# schemat.net
KiCad netlist of a schematic drawn in EAGLE
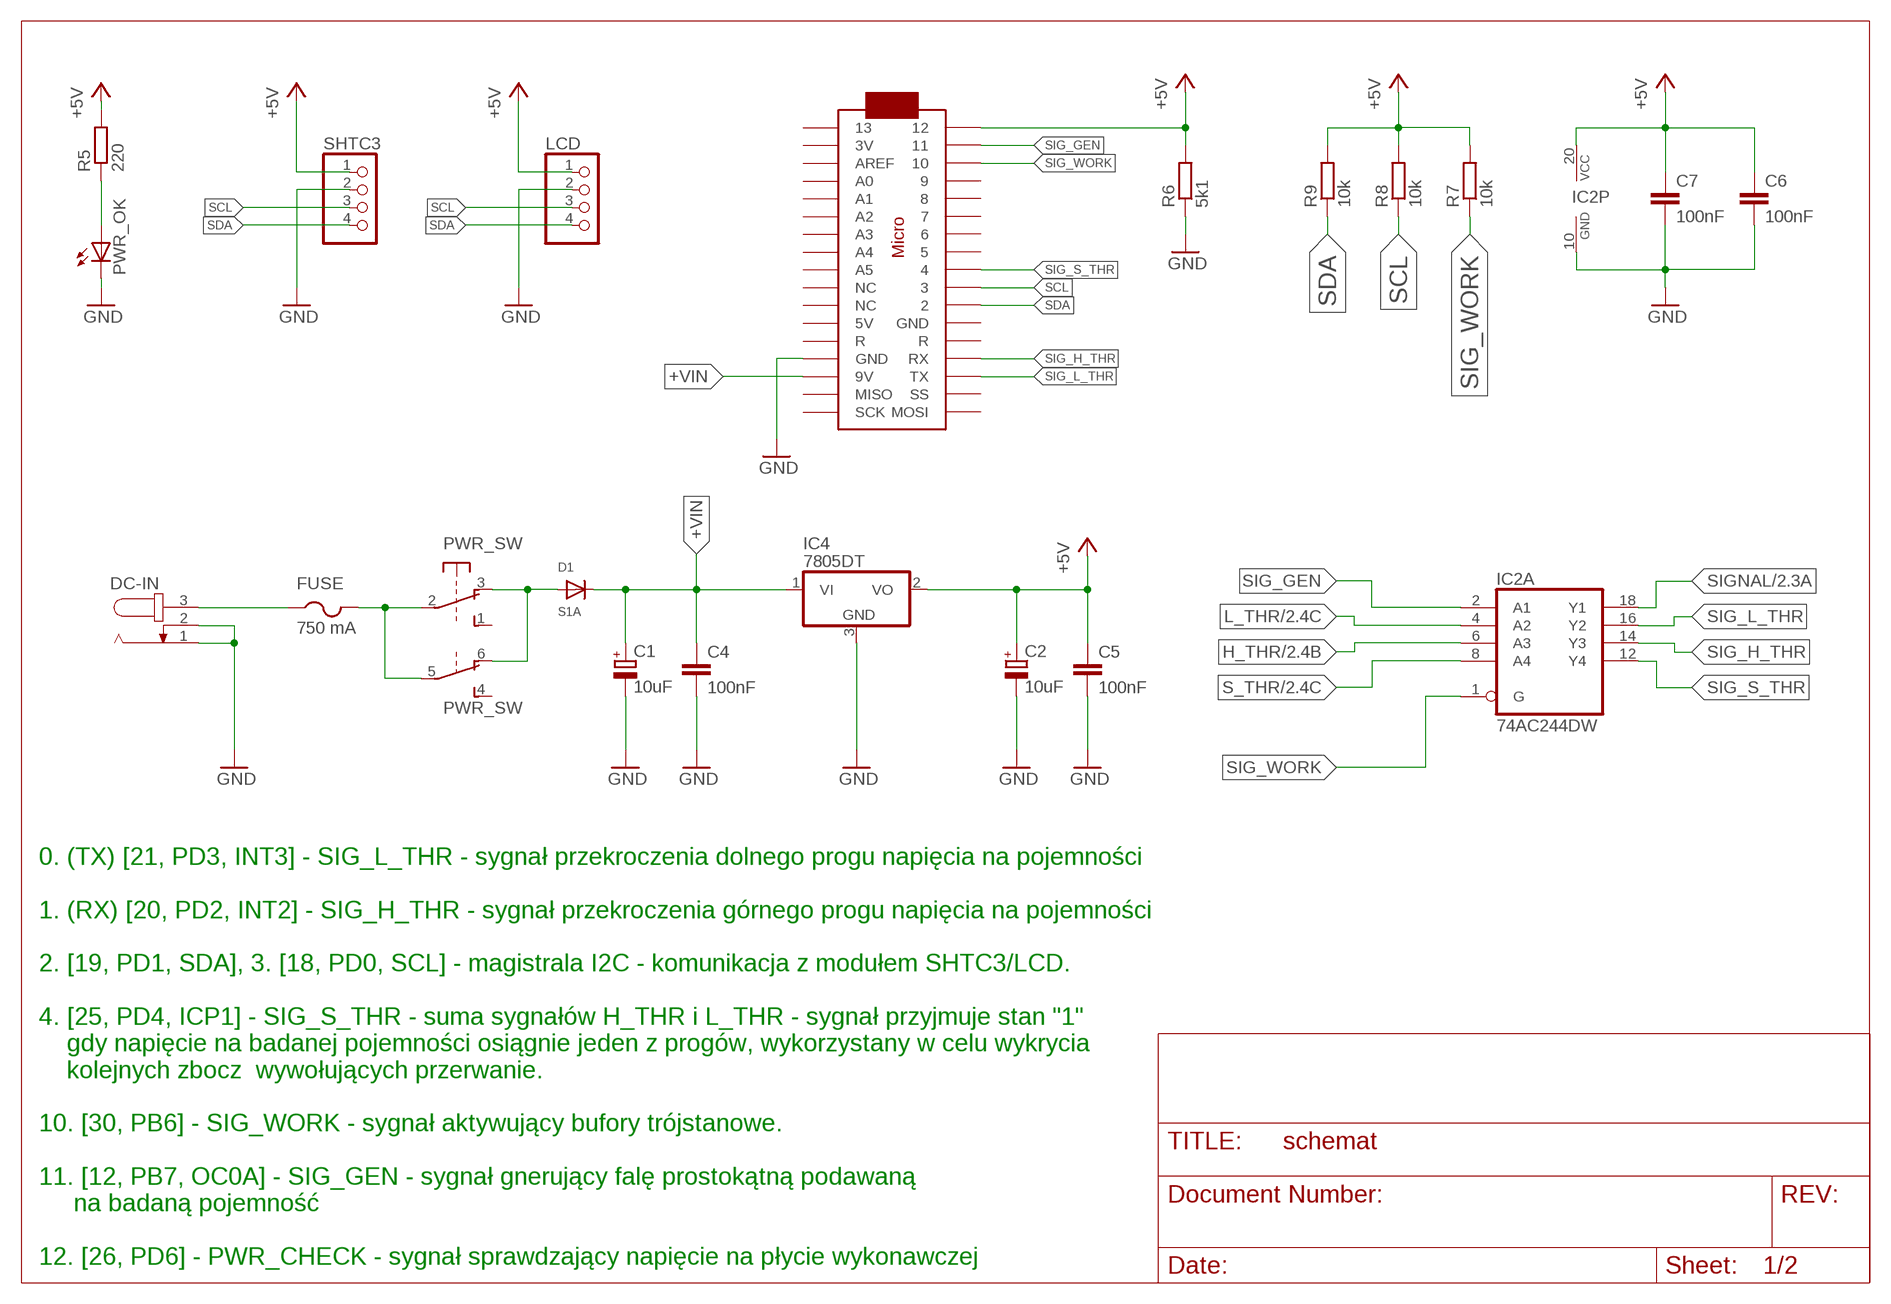
[diagram p0: schematic, sheet 1]
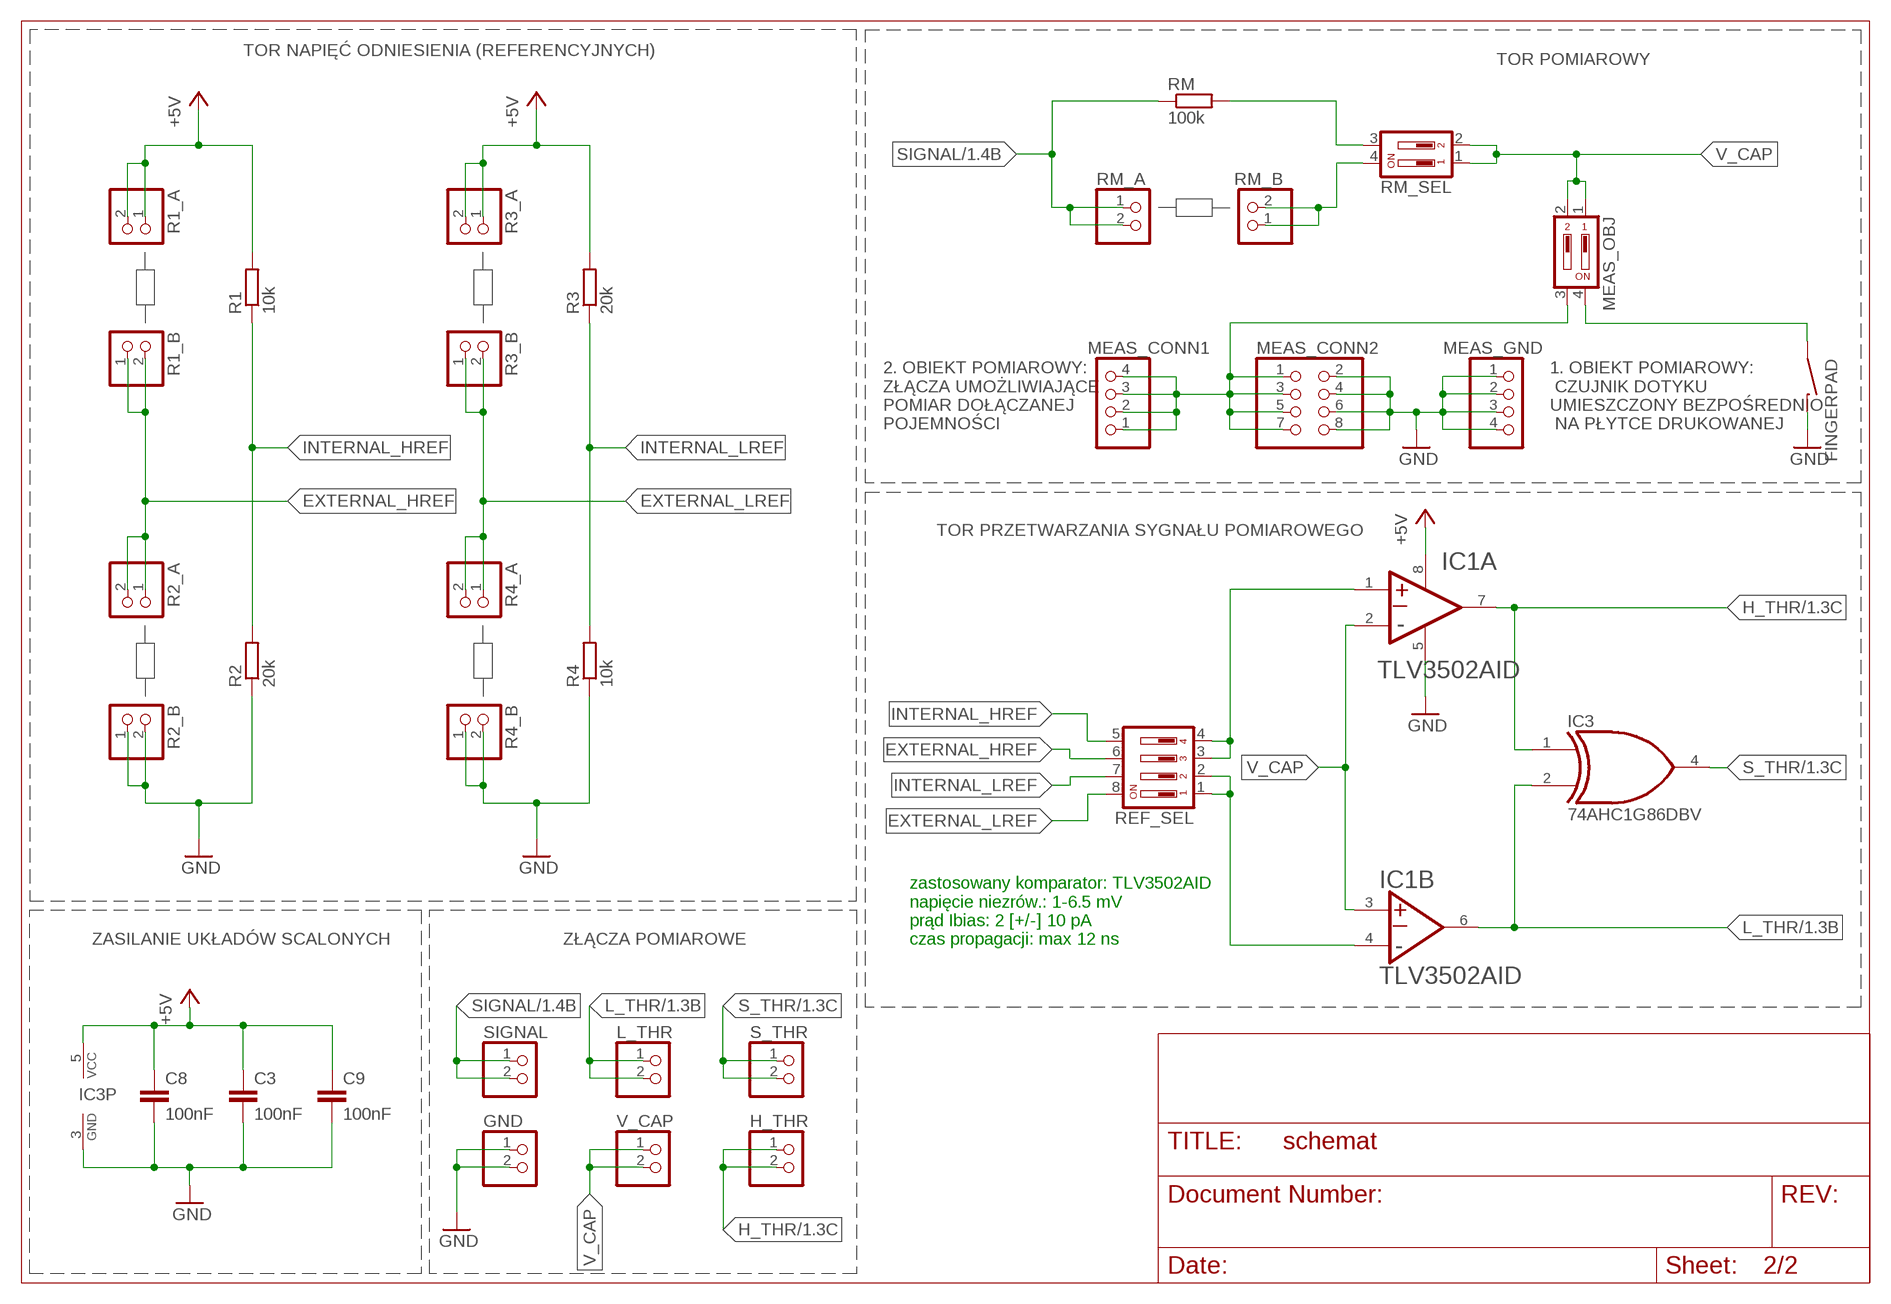
[diagram p1: schematic, sheet 2]

(export (version "E")
  (design (tool "Eeschema 10.0.6"))
  (components
    (comp (ref "C3")
      (value "100nF")
      (footprint "eagle-import:C1206K")
      (libsource (lib "eagle-import") (part "C-EUC1206K"))
    )
    (comp (ref "C8")
      (value "100nF")
      (footprint "eagle-import:C1206K")
      (libsource (lib "eagle-import") (part "C-EUC1206K"))
    )
    (comp (ref "C9")
      (value "100nF")
      (footprint "eagle-import:C1206K")
      (libsource (lib "eagle-import") (part "C-EUC1206K"))
    )
    (comp (ref "FINGERPAD")
      (value "FINGERPAD-2B")
      (footprint "eagle-import:FINGERPAD-2B")
      (libsource (lib "eagle-import") (part "FINGERPAD-2B"))
    )
    (comp (ref "GND")
      (value "PINHD-1X2")
      (footprint "eagle-import:1X02")
      (libsource (lib "eagle-import") (part "PINHD-1X2"))
    )
    (comp (ref "H_THR")
      (value "PINHD-1X2")
      (footprint "eagle-import:1X02")
      (libsource (lib "eagle-import") (part "PINHD-1X2"))
    )
    (comp (ref "IC1")
      (value "TEXAS_INSTRUMENTS_TLV3502AIDTEXAS_INSTRUMENTS_TLV3502AID_0_1")
      (footprint "eagle-import:TEXAS_INSTRUMENTS_TLV3502AID_1")
      (fields
        (field (name "DIGIKEY_PART_NUMBER") "296-18301-5-ND")
        (field (name "MF") "Texas Instruments")
        (field (name "MOUSER_PART_NUMBER") "595-TLV3502AID")
      )
      (libsource (lib "eagle-import") (part "TEXAS_INSTRUMENTS_TLV3502AIDTEXAS_INSTRUMENTS_TLV3502AID_0_1"))
    )
    (comp (ref "IC3")
      (value "74AHC1G86DBV")
      (footprint "eagle-import:SOT23-5")
      (libsource (lib "eagle-import") (part "741G86DBVAHC"))
    )
    (comp (ref "L_THR")
      (value "PINHD-1X2")
      (footprint "eagle-import:1X02")
      (libsource (lib "eagle-import") (part "PINHD-1X2"))
    )
    (comp (ref "MEAS_CONN1")
      (value "PINHD-1X4")
      (footprint "eagle-import:1X04")
      (libsource (lib "eagle-import") (part "PINHD-1X4"))
    )
    (comp (ref "MEAS_CONN2")
      (value "PINHD-2X4")
      (footprint "eagle-import:2X04")
      (libsource (lib "eagle-import") (part "PINHD-2X4"))
    )
    (comp (ref "MEAS_GND")
      (value "PINHD-1X4")
      (footprint "eagle-import:1X04")
      (libsource (lib "eagle-import") (part "PINHD-1X4"))
    )
    (comp (ref "MEAS_OBJ")
      (value "219-02")
      (footprint "eagle-import:CTS-219-02")
      (libsource (lib "eagle-import") (part "219-02"))
    )
    (comp (ref "R1")
      (value "10k")
      (footprint "eagle-import:M1206")
      (libsource (lib "eagle-import") (part "R-EU_M1206"))
    )
    (comp (ref "R1_A")
      (value "PINHD-1X2")
      (footprint "eagle-import:1X02")
      (libsource (lib "eagle-import") (part "PINHD-1X2"))
    )
    (comp (ref "R1_B")
      (value "PINHD-1X2")
      (footprint "eagle-import:1X02")
      (libsource (lib "eagle-import") (part "PINHD-1X2"))
    )
    (comp (ref "R2")
      (value "20k")
      (footprint "eagle-import:M1206")
      (libsource (lib "eagle-import") (part "R-EU_M1206"))
    )
    (comp (ref "R2_A")
      (value "PINHD-1X2")
      (footprint "eagle-import:1X02")
      (libsource (lib "eagle-import") (part "PINHD-1X2"))
    )
    (comp (ref "R2_B")
      (value "PINHD-1X2")
      (footprint "eagle-import:1X02")
      (libsource (lib "eagle-import") (part "PINHD-1X2"))
    )
    (comp (ref "R3")
      (value "20k")
      (footprint "eagle-import:M1206")
      (libsource (lib "eagle-import") (part "R-EU_M1206"))
    )
    (comp (ref "R3_A")
      (value "PINHD-1X2")
      (footprint "eagle-import:1X02")
      (libsource (lib "eagle-import") (part "PINHD-1X2"))
    )
    (comp (ref "R3_B")
      (value "PINHD-1X2")
      (footprint "eagle-import:1X02")
      (libsource (lib "eagle-import") (part "PINHD-1X2"))
    )
    (comp (ref "R4")
      (value "10k")
      (footprint "eagle-import:M1206")
      (libsource (lib "eagle-import") (part "R-EU_M1206"))
    )
    (comp (ref "R4_A")
      (value "PINHD-1X2")
      (footprint "eagle-import:1X02")
      (libsource (lib "eagle-import") (part "PINHD-1X2"))
    )
    (comp (ref "R4_B")
      (value "PINHD-1X2")
      (footprint "eagle-import:1X02")
      (libsource (lib "eagle-import") (part "PINHD-1X2"))
    )
    (comp (ref "REF_SEL")
      (value "219-04")
      (footprint "eagle-import:CTS-219-04")
      (libsource (lib "eagle-import") (part "219-04"))
    )
    (comp (ref "RM")
      (value "100k")
      (footprint "eagle-import:M1206")
      (libsource (lib "eagle-import") (part "R-EU_M1206"))
    )
    (comp (ref "RM_A")
      (value "PINHD-1X2")
      (footprint "eagle-import:1X02")
      (libsource (lib "eagle-import") (part "PINHD-1X2"))
    )
    (comp (ref "RM_B")
      (value "PINHD-1X2")
      (footprint "eagle-import:1X02")
      (libsource (lib "eagle-import") (part "PINHD-1X2"))
    )
    (comp (ref "RM_SEL")
      (value "219-02")
      (footprint "eagle-import:CTS-219-02")
      (libsource (lib "eagle-import") (part "219-02"))
    )
    (comp (ref "SIGNAL")
      (value "PINHD-1X2")
      (footprint "eagle-import:1X02")
      (libsource (lib "eagle-import") (part "PINHD-1X2"))
    )
    (comp (ref "S_THR")
      (value "PINHD-1X2")
      (footprint "eagle-import:1X02")
      (libsource (lib "eagle-import") (part "PINHD-1X2"))
    )
    (comp (ref "V_CAP")
      (value "PINHD-1X2")
      (footprint "eagle-import:1X02")
      (libsource (lib "eagle-import") (part "PINHD-1X2"))
    )
    (comp (ref "C1")
      (value "10uF")
      (footprint "eagle-import:153CLV-0605")
      (libsource (lib "eagle-import") (part "CPOL-EU153CLV-0605"))
    )
    (comp (ref "C2")
      (value "10uF")
      (footprint "eagle-import:153CLV-0605")
      (libsource (lib "eagle-import") (part "CPOL-EU153CLV-0605"))
    )
    (comp (ref "C4")
      (value "100nF")
      (footprint "eagle-import:C1206K")
      (libsource (lib "eagle-import") (part "C-EUC1206K"))
    )
    (comp (ref "C5")
      (value "100nF")
      (footprint "eagle-import:C1206K")
      (libsource (lib "eagle-import") (part "C-EUC1206K"))
    )
    (comp (ref "C6")
      (value "100nF")
      (footprint "eagle-import:C1206K")
      (libsource (lib "eagle-import") (part "C-EUC1206K"))
    )
    (comp (ref "C7")
      (value "100nF")
      (footprint "eagle-import:C1206K")
      (libsource (lib "eagle-import") (part "C-EUC1206K"))
    )
    (comp (ref "D1")
      (value "S1A")
      (footprint "eagle-import:SMADIODE")
      (libsource (lib "eagle-import") (part "DIODESMA"))
    )
    (comp (ref "DC-IN")
      (value "JACK-PLUG1")
      (footprint "eagle-import:SPC4078")
      (libsource (lib "eagle-import") (part "JACK-PLUG1"))
    )
    (comp (ref "FUSE")
      (value "750 mA")
      (footprint "eagle-import:1812")
      (libsource (lib "eagle-import") (part "PTCFUSE-1812"))
    )
    (comp (ref "IC2")
      (value "74AC244DW")
      (footprint "eagle-import:SO20W")
      (libsource (lib "eagle-import") (part "74244DWAC"))
    )
    (comp (ref "IC4")
      (value "7805DT")
      (footprint "eagle-import:TO252")
      (libsource (lib "eagle-import") (part "78DT05"))
    )
    (comp (ref "LCD")
      (value "PINHD-1X4")
      (footprint "eagle-import:1X04")
      (libsource (lib "eagle-import") (part "PINHD-1X4"))
    )
    (comp (ref "PWR_OK")
      (value "LEDSMT1206")
      (footprint "eagle-import:1206")
      (libsource (lib "eagle-import") (part "LEDSMT1206"))
    )
    (comp (ref "PWR_SW")
      (value "9077-2")
      (footprint "eagle-import:9077-2")
      (libsource (lib "eagle-import") (part "9077-2"))
    )
    (comp (ref "R5")
      (value "220")
      (footprint "eagle-import:R1206")
      (libsource (lib "eagle-import") (part "R-EU_R1206"))
    )
    (comp (ref "R6")
      (value "5k1")
      (footprint "eagle-import:R1206")
      (libsource (lib "eagle-import") (part "R-EU_R1206"))
    )
    (comp (ref "R7")
      (value "10k")
      (footprint "eagle-import:R1206")
      (libsource (lib "eagle-import") (part "R-EU_R1206"))
    )
    (comp (ref "R8")
      (value "10k")
      (footprint "eagle-import:R1206")
      (libsource (lib "eagle-import") (part "R-EU_R1206"))
    )
    (comp (ref "R9")
      (value "10k")
      (footprint "eagle-import:R1206")
      (libsource (lib "eagle-import") (part "R-EU_R1206"))
    )
    (comp (ref "SHTC3")
      (value "PINHD-1X4")
      (footprint "eagle-import:1X04")
      (libsource (lib "eagle-import") (part "PINHD-1X4"))
    )
    (comp (ref "U$1")
      (value "ARDUINOMICRO")
      (footprint "eagle-import:ARDUINOMICRO")
      (libsource (lib "eagle-import") (part "ARDUINOMICRO"))
    )
  )
  (nets
    (net (code "1") (name "+5V") (class "Default")
      (node (ref "C2") (pin "+") (pinfunction "+_+") (pintype "passive"))
      (node (ref "C3") (pin "1") (pinfunction "1_1") (pintype "passive"))
      (node (ref "C5") (pin "1") (pinfunction "1_1") (pintype "passive"))
      (node (ref "C6") (pin "1") (pinfunction "1_1") (pintype "passive"))
      (node (ref "C7") (pin "1") (pinfunction "1_1") (pintype "passive"))
      (node (ref "C8") (pin "1") (pinfunction "1_1") (pintype "passive"))
      (node (ref "C9") (pin "1") (pinfunction "1_1") (pintype "passive"))
      (node (ref "IC1") (pin "8") (pinfunction "V+_8") (pintype "power_in"))
      (node (ref "IC2") (pin "20") (pinfunction "VCC_20") (pintype "power_in"))
      (node (ref "IC3") (pin "5") (pinfunction "VCC_5") (pintype "power_in"))
      (node (ref "IC4") (pin "2") (pinfunction "VO_2") (pintype "passive"))
      (node (ref "LCD") (pin "1") (pinfunction "1_1") (pintype "passive"))
      (node (ref "R1") (pin "2") (pinfunction "2_2") (pintype "passive"))
      (node (ref "R1_A") (pin "1") (pinfunction "1_1") (pintype "passive"))
      (node (ref "R1_A") (pin "2") (pinfunction "2_2") (pintype "passive"))
      (node (ref "R3") (pin "2") (pinfunction "2_2") (pintype "passive"))
      (node (ref "R3_A") (pin "1") (pinfunction "1_1") (pintype "passive"))
      (node (ref "R3_A") (pin "2") (pinfunction "2_2") (pintype "passive"))
      (node (ref "R5") (pin "2") (pinfunction "2_2") (pintype "passive"))
      (node (ref "R6") (pin "2") (pinfunction "2_2") (pintype "passive"))
      (node (ref "R7") (pin "2") (pinfunction "2_2") (pintype "passive"))
      (node (ref "R8") (pin "2") (pinfunction "2_2") (pintype "passive"))
      (node (ref "R9") (pin "2") (pinfunction "2_2") (pintype "passive"))
      (node (ref "SHTC3") (pin "1") (pinfunction "1_1") (pintype "passive"))
      (node (ref "U$1") (pin "P$1") (pinfunction "12_P$1") (pintype "bidirectional"))
    )
    (net (code "2") (name "+VIN") (class "Default")
      (node (ref "C1") (pin "+") (pinfunction "+_+") (pintype "passive"))
      (node (ref "C4") (pin "1") (pinfunction "1_1") (pintype "passive"))
      (node (ref "D1") (pin "C") (pinfunction "C_C") (pintype "passive"))
      (node (ref "IC4") (pin "1") (pinfunction "VI_1") (pintype "input"))
      (node (ref "U$1") (pin "P$20") (pinfunction "9V_P$20") (pintype "bidirectional"))
    )
    (net (code "3") (name "EXTERNAL_HREF") (class "Default")
      (node (ref "R1_B") (pin "1") (pinfunction "1_1") (pintype "passive"))
      (node (ref "R1_B") (pin "2") (pinfunction "2_2") (pintype "passive"))
      (node (ref "R2_A") (pin "1") (pinfunction "1_1") (pintype "passive"))
      (node (ref "R2_A") (pin "2") (pinfunction "2_2") (pintype "passive"))
      (node (ref "REF_SEL") (pin "6") (pinfunction "6_6") (pintype "passive"))
    )
    (net (code "4") (name "EXTERNAL_LREF") (class "Default")
      (node (ref "R3_B") (pin "1") (pinfunction "1_1") (pintype "passive"))
      (node (ref "R3_B") (pin "2") (pinfunction "2_2") (pintype "passive"))
      (node (ref "R4_A") (pin "1") (pinfunction "1_1") (pintype "passive"))
      (node (ref "R4_A") (pin "2") (pinfunction "2_2") (pintype "passive"))
      (node (ref "REF_SEL") (pin "8") (pinfunction "8_8") (pintype "passive"))
    )
    (net (code "5") (name "GND") (class "Default")
      (node (ref "C1") (pin "-") (pinfunction "-_-") (pintype "passive"))
      (node (ref "C2") (pin "-") (pinfunction "-_-") (pintype "passive"))
      (node (ref "C3") (pin "2") (pinfunction "2_2") (pintype "passive"))
      (node (ref "C4") (pin "2") (pinfunction "2_2") (pintype "passive"))
      (node (ref "C5") (pin "2") (pinfunction "2_2") (pintype "passive"))
      (node (ref "C6") (pin "2") (pinfunction "2_2") (pintype "passive"))
      (node (ref "C7") (pin "2") (pinfunction "2_2") (pintype "passive"))
      (node (ref "C8") (pin "2") (pinfunction "2_2") (pintype "passive"))
      (node (ref "C9") (pin "2") (pinfunction "2_2") (pintype "passive"))
      (node (ref "DC-IN") (pin "1") (pinfunction "1_1") (pintype "passive"))
      (node (ref "DC-IN") (pin "2") (pinfunction "2_2") (pintype "passive"))
      (node (ref "FINGERPAD") (pin "2") (pinfunction "2_2") (pintype "passive"))
      (node (ref "GND") (pin "1") (pinfunction "1_1") (pintype "passive"))
      (node (ref "GND") (pin "2") (pinfunction "2_2") (pintype "passive"))
      (node (ref "IC1") (pin "5") (pinfunction "V−_5") (pintype "power_in"))
      (node (ref "IC2") (pin "10") (pinfunction "GND_10") (pintype "power_in"))
      (node (ref "IC3") (pin "3") (pinfunction "GND_3") (pintype "power_in"))
      (node (ref "IC4") (pin "3") (pinfunction "GND_3") (pintype "passive"))
      (node (ref "LCD") (pin "2") (pinfunction "2_2") (pintype "passive"))
      (node (ref "MEAS_CONN2") (pin "2") (pinfunction "2_2") (pintype "passive"))
      (node (ref "MEAS_CONN2") (pin "4") (pinfunction "4_4") (pintype "passive"))
      (node (ref "MEAS_CONN2") (pin "6") (pinfunction "6_6") (pintype "passive"))
      (node (ref "MEAS_CONN2") (pin "8") (pinfunction "8_8") (pintype "passive"))
      (node (ref "MEAS_GND") (pin "1") (pinfunction "1_1") (pintype "passive"))
      (node (ref "MEAS_GND") (pin "2") (pinfunction "2_2") (pintype "passive"))
      (node (ref "MEAS_GND") (pin "3") (pinfunction "3_3") (pintype "passive"))
      (node (ref "MEAS_GND") (pin "4") (pinfunction "4_4") (pintype "passive"))
      (node (ref "PWR_OK") (pin "C") (pinfunction "C_C") (pintype "passive"))
      (node (ref "R2") (pin "1") (pinfunction "1_1") (pintype "passive"))
      (node (ref "R2_B") (pin "1") (pinfunction "1_1") (pintype "passive"))
      (node (ref "R2_B") (pin "2") (pinfunction "2_2") (pintype "passive"))
      (node (ref "R4") (pin "1") (pinfunction "1_1") (pintype "passive"))
      (node (ref "R4_B") (pin "1") (pinfunction "1_1") (pintype "passive"))
      (node (ref "R4_B") (pin "2") (pinfunction "2_2") (pintype "passive"))
      (node (ref "R6") (pin "1") (pinfunction "1_1") (pintype "passive"))
      (node (ref "SHTC3") (pin "2") (pinfunction "2_2") (pintype "passive"))
      (node (ref "U$1") (pin "P$12") (pinfunction "GND_P$12") (pintype "bidirectional"))
    )
    (net (code "6") (name "H_THR") (class "Default")
      (node (ref "H_THR") (pin "1") (pinfunction "1_1") (pintype "passive"))
      (node (ref "H_THR") (pin "2") (pinfunction "2_2") (pintype "passive"))
      (node (ref "IC1") (pin "7") (pinfunction "OUT_A_7") (pintype "passive"))
      (node (ref "IC2") (pin "6") (pinfunction "A3_6") (pintype "input"))
      (node (ref "IC3") (pin "1") (pinfunction "I0_1") (pintype "input"))
    )
    (net (code "7") (name "INTERNAL_HREF") (class "Default")
      (node (ref "R1") (pin "1") (pinfunction "1_1") (pintype "passive"))
      (node (ref "R2") (pin "2") (pinfunction "2_2") (pintype "passive"))
      (node (ref "REF_SEL") (pin "5") (pinfunction "5_5") (pintype "passive"))
    )
    (net (code "8") (name "INTERNAL_LREF") (class "Default")
      (node (ref "R3") (pin "1") (pinfunction "1_1") (pintype "passive"))
      (node (ref "R4") (pin "2") (pinfunction "2_2") (pintype "passive"))
      (node (ref "REF_SEL") (pin "7") (pinfunction "7_7") (pintype "passive"))
    )
    (net (code "9") (name "L_THR") (class "Default")
      (node (ref "IC1") (pin "6") (pinfunction "OUT_B_6") (pintype "passive"))
      (node (ref "IC2") (pin "4") (pinfunction "A2_4") (pintype "input"))
      (node (ref "IC3") (pin "2") (pinfunction "I1_2") (pintype "input"))
      (node (ref "L_THR") (pin "1") (pinfunction "1_1") (pintype "passive"))
      (node (ref "L_THR") (pin "2") (pinfunction "2_2") (pintype "passive"))
    )
    (net (code "10") (name "Net-(DC-IN-Pad3)") (class "Default")
      (node (ref "DC-IN") (pin "3") (pinfunction "3_3") (pintype "passive"))
      (node (ref "FUSE") (pin "1") (pinfunction "1_1") (pintype "passive"))
    )
    (net (code "11") (name "Net-(FINGERPAD-Pad1)") (class "Default")
      (node (ref "FINGERPAD") (pin "1") (pinfunction "1_1") (pintype "passive"))
      (node (ref "MEAS_OBJ") (pin "4") (pinfunction "4_4") (pintype "passive"))
    )
    (net (code "12") (name "Net-(IC1A-+IN_A)") (class "Default")
      (node (ref "IC1") (pin "1") (pinfunction "+IN_A_1") (pintype "tri_state"))
      (node (ref "REF_SEL") (pin "3") (pinfunction "3_3") (pintype "passive"))
      (node (ref "REF_SEL") (pin "4") (pinfunction "4_4") (pintype "passive"))
    )
    (net (code "13") (name "Net-(IC1B-−IN_B)") (class "Default")
      (node (ref "IC1") (pin "4") (pinfunction "−IN_B_4") (pintype "tri_state"))
      (node (ref "REF_SEL") (pin "1") (pinfunction "1_1") (pintype "passive"))
      (node (ref "REF_SEL") (pin "2") (pinfunction "2_2") (pintype "passive"))
    )
    (net (code "14") (name "Net-(MEAS_CONN1-Pad1)") (class "Default")
      (node (ref "MEAS_CONN1") (pin "1") (pinfunction "1_1") (pintype "passive"))
      (node (ref "MEAS_CONN1") (pin "2") (pinfunction "2_2") (pintype "passive"))
      (node (ref "MEAS_CONN1") (pin "3") (pinfunction "3_3") (pintype "passive"))
      (node (ref "MEAS_CONN1") (pin "4") (pinfunction "4_4") (pintype "passive"))
      (node (ref "MEAS_CONN2") (pin "1") (pinfunction "1_1") (pintype "passive"))
      (node (ref "MEAS_CONN2") (pin "3") (pinfunction "3_3") (pintype "passive"))
      (node (ref "MEAS_CONN2") (pin "5") (pinfunction "5_5") (pintype "passive"))
      (node (ref "MEAS_CONN2") (pin "7") (pinfunction "7_7") (pintype "passive"))
      (node (ref "MEAS_OBJ") (pin "3") (pinfunction "3_3") (pintype "passive"))
    )
    (net (code "15") (name "Net-(PWR_OK-PadA)") (class "Default")
      (node (ref "PWR_OK") (pin "A") (pinfunction "A_A") (pintype "passive"))
      (node (ref "R5") (pin "1") (pinfunction "1_1") (pintype "passive"))
    )
    (net (code "16") (name "Net-(PWR_SWA-O)") (class "Default")
      (node (ref "D1") (pin "A") (pinfunction "A_A") (pintype "passive"))
      (node (ref "PWR_SW") (pin "3") (pinfunction "O_3") (pintype "passive"))
      (node (ref "PWR_SW") (pin "6") (pinfunction "O_6") (pintype "passive"))
    )
    (net (code "17") (name "Net-(PWR_SWA-P)") (class "Default")
      (node (ref "FUSE") (pin "2") (pinfunction "2_2") (pintype "passive"))
      (node (ref "PWR_SW") (pin "2") (pinfunction "P_2") (pintype "passive"))
      (node (ref "PWR_SW") (pin "5") (pinfunction "P_5") (pintype "passive"))
    )
    (net (code "18") (name "Net-(RM-Pad2)") (class "Default")
      (node (ref "RM") (pin "2") (pinfunction "2_2") (pintype "passive"))
      (node (ref "RM_SEL") (pin "3") (pinfunction "3_3") (pintype "passive"))
    )
    (net (code "19") (name "Net-(RM_B-Pad1)") (class "Default")
      (node (ref "RM_B") (pin "1") (pinfunction "1_1") (pintype "passive"))
      (node (ref "RM_B") (pin "2") (pinfunction "2_2") (pintype "passive"))
      (node (ref "RM_SEL") (pin "4") (pinfunction "4_4") (pintype "passive"))
    )
    (net (code "20") (name "SCL") (class "Default")
      (node (ref "LCD") (pin "3") (pinfunction "3_3") (pintype "passive"))
      (node (ref "R8") (pin "1") (pinfunction "1_1") (pintype "passive"))
      (node (ref "SHTC3") (pin "3") (pinfunction "3_3") (pintype "passive"))
      (node (ref "U$1") (pin "P$10") (pinfunction "3_P$10") (pintype "bidirectional"))
    )
    (net (code "21") (name "SDA") (class "Default")
      (node (ref "LCD") (pin "4") (pinfunction "4_4") (pintype "passive"))
      (node (ref "R9") (pin "1") (pinfunction "1_1") (pintype "passive"))
      (node (ref "SHTC3") (pin "4") (pinfunction "4_4") (pintype "passive"))
      (node (ref "U$1") (pin "P$11") (pinfunction "2_P$11") (pintype "bidirectional"))
    )
    (net (code "22") (name "SIGNAL") (class "Default")
      (node (ref "IC2") (pin "18") (pinfunction "Y1_18") (pintype "tri_state"))
      (node (ref "RM") (pin "1") (pinfunction "1_1") (pintype "passive"))
      (node (ref "RM_A") (pin "1") (pinfunction "1_1") (pintype "passive"))
      (node (ref "RM_A") (pin "2") (pinfunction "2_2") (pintype "passive"))
      (node (ref "SIGNAL") (pin "1") (pinfunction "1_1") (pintype "passive"))
      (node (ref "SIGNAL") (pin "2") (pinfunction "2_2") (pintype "passive"))
    )
    (net (code "23") (name "SIG_GEN") (class "Default")
      (node (ref "IC2") (pin "2") (pinfunction "A1_2") (pintype "input"))
      (node (ref "U$1") (pin "P$2") (pinfunction "11_P$2") (pintype "bidirectional"))
    )
    (net (code "24") (name "SIG_H_THR") (class "Default")
      (node (ref "IC2") (pin "14") (pinfunction "Y3_14") (pintype "tri_state"))
      (node (ref "U$1") (pin "P$14") (pinfunction "RX_P$14") (pintype "bidirectional"))
    )
    (net (code "25") (name "SIG_L_THR") (class "Default")
      (node (ref "IC2") (pin "16") (pinfunction "Y2_16") (pintype "tri_state"))
      (node (ref "U$1") (pin "P$15") (pinfunction "TX_P$15") (pintype "bidirectional"))
    )
    (net (code "26") (name "SIG_S_THR") (class "Default")
      (node (ref "IC2") (pin "12") (pinfunction "Y4_12") (pintype "tri_state"))
      (node (ref "U$1") (pin "P$9") (pinfunction "4_P$9") (pintype "bidirectional"))
    )
    (net (code "27") (name "SIG_WORK") (class "Default")
      (node (ref "IC2") (pin "1") (pinfunction "G_1") (pintype "input"))
      (node (ref "R7") (pin "1") (pinfunction "1_1") (pintype "passive"))
      (node (ref "U$1") (pin "P$3") (pinfunction "10_P$3") (pintype "bidirectional"))
    )
    (net (code "28") (name "S_THR") (class "Default")
      (node (ref "IC2") (pin "8") (pinfunction "A4_8") (pintype "input"))
      (node (ref "IC3") (pin "4") (pinfunction "O_4") (pintype "output"))
      (node (ref "S_THR") (pin "1") (pinfunction "1_1") (pintype "passive"))
      (node (ref "S_THR") (pin "2") (pinfunction "2_2") (pintype "passive"))
    )
    (net (code "29") (name "V_CAP") (class "Default")
      (node (ref "IC1") (pin "2") (pinfunction "−IN_A_2") (pintype "tri_state"))
      (node (ref "IC1") (pin "3") (pinfunction "+IN_B_3") (pintype "tri_state"))
      (node (ref "MEAS_OBJ") (pin "1") (pinfunction "1_1") (pintype "passive"))
      (node (ref "MEAS_OBJ") (pin "2") (pinfunction "2_2") (pintype "passive"))
      (node (ref "RM_SEL") (pin "1") (pinfunction "1_1") (pintype "passive"))
      (node (ref "RM_SEL") (pin "2") (pinfunction "2_2") (pintype "passive"))
      (node (ref "V_CAP") (pin "1") (pinfunction "1_1") (pintype "passive"))
      (node (ref "V_CAP") (pin "2") (pinfunction "2_2") (pintype "passive"))
    )
    (net (code "30") (name "unconnected-(PWR_SWA-S-Pad1)") (class "Default")
      (node (ref "PWR_SW") (pin "1") (pinfunction "S_1") (pintype "passive"))
    )
    (net (code "31") (name "unconnected-(PWR_SWB-S-Pad4)") (class "Default")
      (node (ref "PWR_SW") (pin "4") (pinfunction "S_4") (pintype "passive"))
    )
    (net (code "32") (name "unconnected-(U$1-3V-PadP$33)") (class "Default")
      (node (ref "U$1") (pin "P$33") (pinfunction "3V_P$33") (pintype "bidirectional"))
    )
    (net (code "33") (name "unconnected-(U$1-5-PadP$8)") (class "Default")
      (node (ref "U$1") (pin "P$8") (pinfunction "5_P$8") (pintype "bidirectional"))
    )
    (net (code "34") (name "unconnected-(U$1-5V-PadP$23)") (class "Default")
      (node (ref "U$1") (pin "P$23") (pinfunction "5V_P$23") (pintype "bidirectional"))
    )
    (net (code "35") (name "unconnected-(U$1-6-PadP$7)") (class "Default")
      (node (ref "U$1") (pin "P$7") (pinfunction "6_P$7") (pintype "bidirectional"))
    )
    (net (code "36") (name "unconnected-(U$1-7-PadP$6)") (class "Default")
      (node (ref "U$1") (pin "P$6") (pinfunction "7_P$6") (pintype "bidirectional"))
    )
    (net (code "37") (name "unconnected-(U$1-8-PadP$5)") (class "Default")
      (node (ref "U$1") (pin "P$5") (pinfunction "8_P$5") (pintype "bidirectional"))
    )
    (net (code "38") (name "unconnected-(U$1-9-PadP$4)") (class "Default")
      (node (ref "U$1") (pin "P$4") (pinfunction "9_P$4") (pintype "bidirectional"))
    )
    (net (code "39") (name "unconnected-(U$1-13-PadP$34)") (class "Default")
      (node (ref "U$1") (pin "P$34") (pinfunction "13_P$34") (pintype "bidirectional"))
    )
    (net (code "40") (name "unconnected-(U$1-A0-PadP$31)") (class "Default")
      (node (ref "U$1") (pin "P$31") (pinfunction "A0_P$31") (pintype "bidirectional"))
    )
    (net (code "41") (name "unconnected-(U$1-A1-PadP$30)") (class "Default")
      (node (ref "U$1") (pin "P$30") (pinfunction "A1_P$30") (pintype "bidirectional"))
    )
    (net (code "42") (name "unconnected-(U$1-A2-PadP$29)") (class "Default")
      (node (ref "U$1") (pin "P$29") (pinfunction "A2_P$29") (pintype "bidirectional"))
    )
    (net (code "43") (name "unconnected-(U$1-A3-PadP$28)") (class "Default")
      (node (ref "U$1") (pin "P$28") (pinfunction "A3_P$28") (pintype "bidirectional"))
    )
    (net (code "44") (name "unconnected-(U$1-A4-PadP$27)") (class "Default")
      (node (ref "U$1") (pin "P$27") (pinfunction "A4_P$27") (pintype "bidirectional"))
    )
    (net (code "45") (name "unconnected-(U$1-A5-PadP$26)") (class "Default")
      (node (ref "U$1") (pin "P$26") (pinfunction "A5_P$26") (pintype "bidirectional"))
    )
    (net (code "46") (name "unconnected-(U$1-AREF-PadP$32)") (class "Default")
      (node (ref "U$1") (pin "P$32") (pinfunction "AREF_P$32") (pintype "bidirectional"))
    )
    (net (code "47") (name "unconnected-(U$1-GND-PadP$21)") (class "Default")
      (node (ref "U$1") (pin "P$21") (pinfunction "GND_P$21") (pintype "bidirectional"))
    )
    (net (code "48") (name "unconnected-(U$1-MISO-PadP$19)") (class "Default")
      (node (ref "U$1") (pin "P$19") (pinfunction "MISO_P$19") (pintype "bidirectional"))
    )
    (net (code "49") (name "unconnected-(U$1-MOSI-PadP$17)") (class "Default")
      (node (ref "U$1") (pin "P$17") (pinfunction "MOSI_P$17") (pintype "bidirectional"))
    )
    (net (code "50") (name "unconnected-(U$1-NC-PadP$24)") (class "Default")
      (node (ref "U$1") (pin "P$24") (pinfunction "NC_P$24") (pintype "bidirectional"))
    )
    (net (code "51") (name "unconnected-(U$1-NC-PadP$25)") (class "Default")
      (node (ref "U$1") (pin "P$25") (pinfunction "NC_P$25") (pintype "bidirectional"))
    )
    (net (code "52") (name "unconnected-(U$1-R-PadP$13)") (class "Default")
      (node (ref "U$1") (pin "P$13") (pinfunction "R_P$13") (pintype "bidirectional"))
    )
    (net (code "53") (name "unconnected-(U$1-R-PadP$22)") (class "Default")
      (node (ref "U$1") (pin "P$22") (pinfunction "R_P$22") (pintype "bidirectional"))
    )
    (net (code "54") (name "unconnected-(U$1-SCK-PadP$18)") (class "Default")
      (node (ref "U$1") (pin "P$18") (pinfunction "SCK_P$18") (pintype "bidirectional"))
    )
    (net (code "55") (name "unconnected-(U$1-SS-PadP$16)") (class "Default")
      (node (ref "U$1") (pin "P$16") (pinfunction "SS_P$16") (pintype "bidirectional"))
    )
  )
)
